# Adafruit_Wii_Nunchuck_Breakout_Adapter.net
KiCad netlist of a schematic drawn in EAGLE
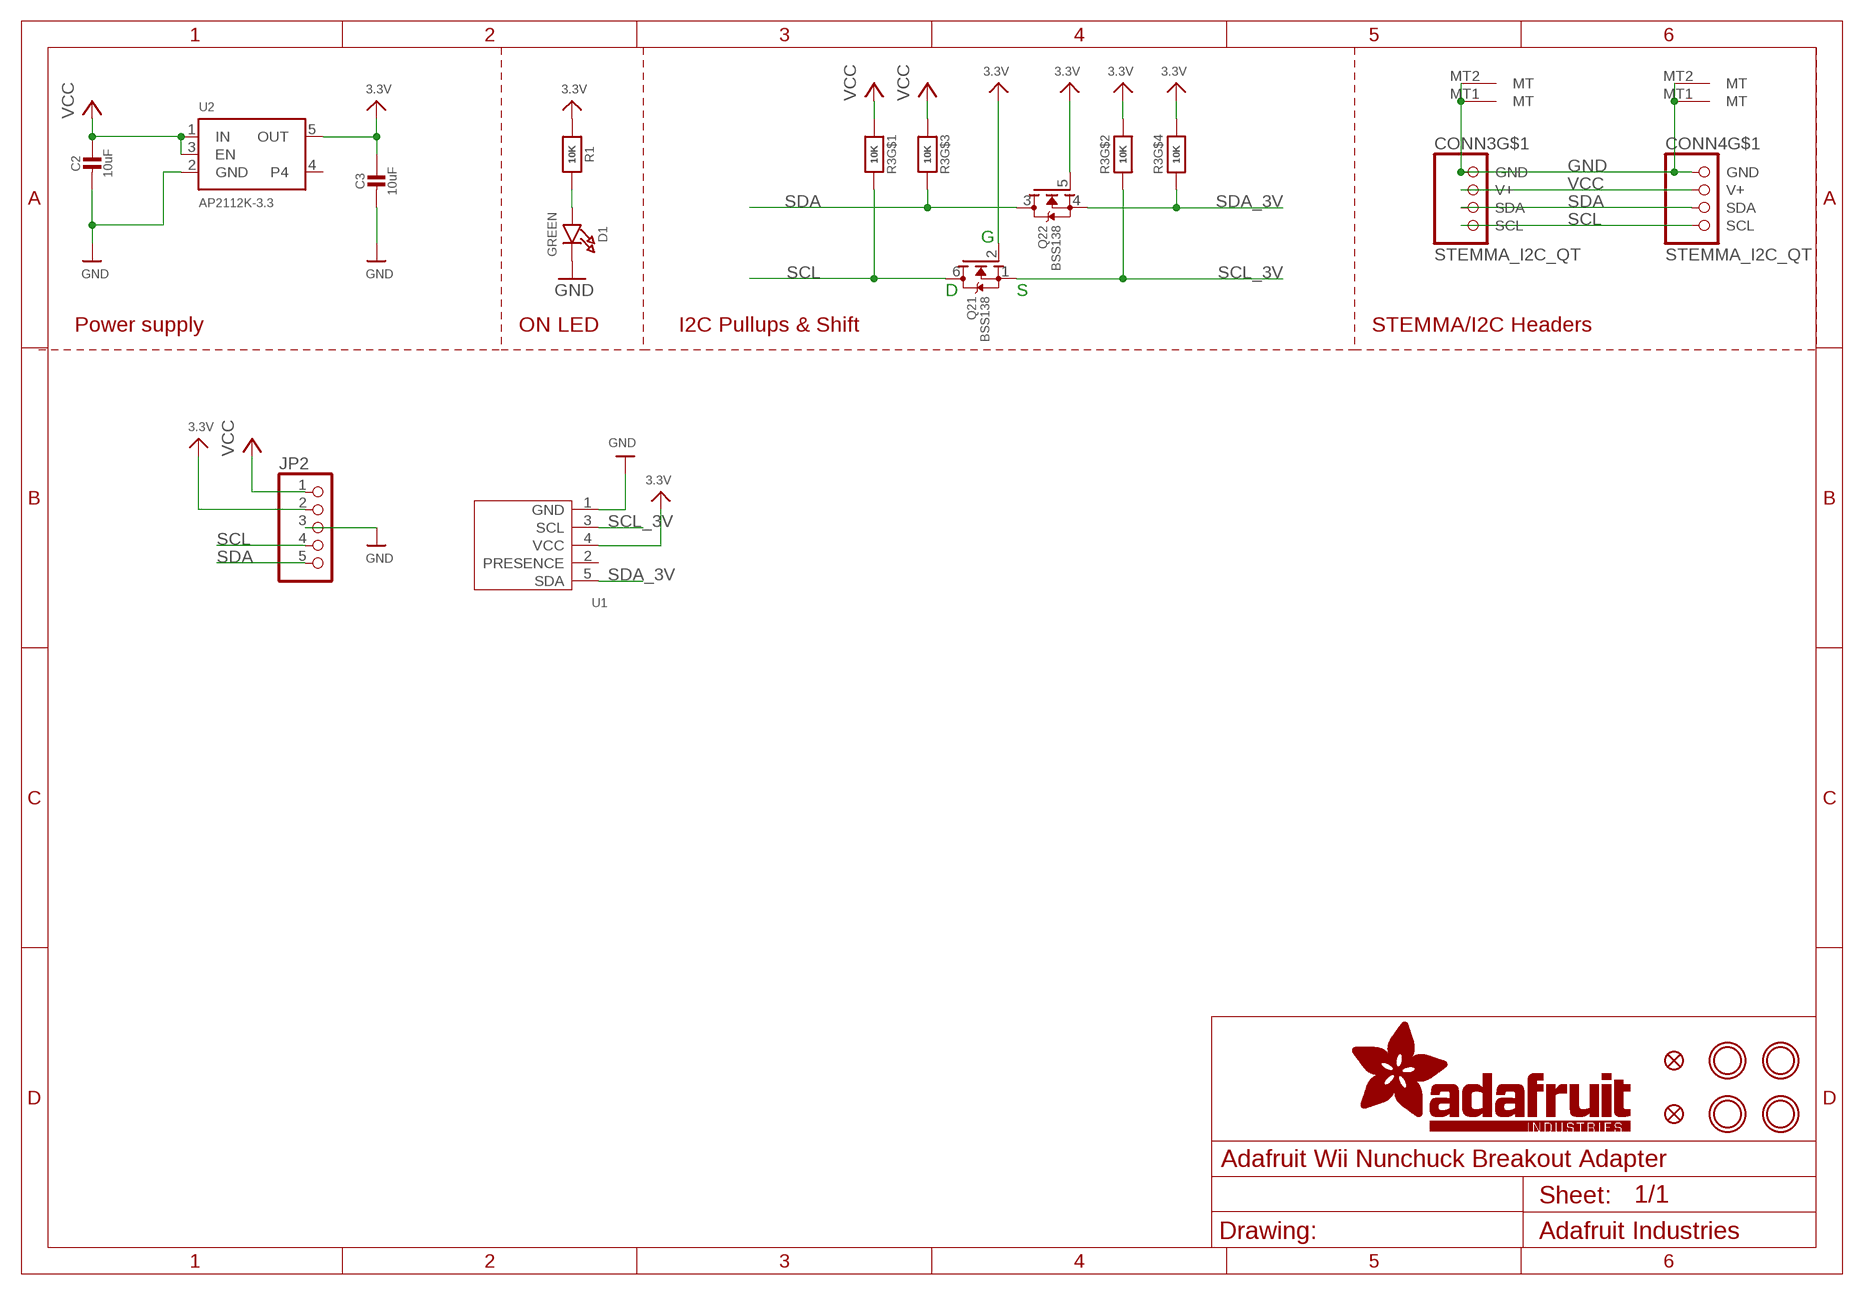
[diagram p0: schematic, sheet 1]

(export (version "E")
  (design (tool "Eeschema 10.0.6"))
  (components
    (comp (ref "C2")
      (value "10uF")
      (footprint "eagle-import:0805-NO")
      (libsource (lib "eagle-import") (part "CAP_CERAMIC0805-NOOUTLINE"))
    )
    (comp (ref "C3")
      (value "10uF")
      (footprint "eagle-import:0805-NO")
      (libsource (lib "eagle-import") (part "CAP_CERAMIC0805-NOOUTLINE"))
    )
    (comp (ref "CONN3")
      (value "STEMMA_I2C_QT")
      (footprint "eagle-import:JST_SH4")
      (libsource (lib "eagle-import") (part "STEMMA_I2C_QT"))
    )
    (comp (ref "CONN4")
      (value "STEMMA_I2C_QT")
      (footprint "eagle-import:JST_SH4")
      (libsource (lib "eagle-import") (part "STEMMA_I2C_QT"))
    )
    (comp (ref "D1")
      (value "GREEN")
      (footprint "eagle-import:CHIPLED_0603_NOOUTLINE")
      (libsource (lib "eagle-import") (part "LED0603_NOOUTLINE"))
    )
    (comp (ref "FID3")
      (value "FIDUCIAL_1MM")
      (footprint "eagle-import:FIDUCIAL_1MM")
      (libsource (lib "eagle-import") (part "FIDUCIAL_1MM"))
    )
    (comp (ref "FID4")
      (value "FIDUCIAL_1MM")
      (footprint "eagle-import:FIDUCIAL_1MM")
      (libsource (lib "eagle-import") (part "FIDUCIAL_1MM"))
    )
    (comp (ref "JP2")
      (value "HEADER-1X570MIL")
      (footprint "eagle-import:1X05_ROUND_70")
      (libsource (lib "eagle-import") (part "HEADER-1X570MIL"))
    )
    (comp (ref "Q2")
      (value "BSS138")
      (footprint "eagle-import:SOT363")
      (libsource (lib "eagle-import") (part "MOSFET-N_DUAL"))
    )
    (comp (ref "R1")
      (value "10K")
      (footprint "eagle-import:0603-NO")
      (libsource (lib "eagle-import") (part "RESISTOR_0603_NOOUT"))
    )
    (comp (ref "R3")
      (value "10K")
      (footprint "eagle-import:RESPACK_4X0603")
      (libsource (lib "eagle-import") (part "RESISTOR_4PACK"))
    )
    (comp (ref "U$1")
      (value "MOUNTINGHOLE2.5")
      (footprint "eagle-import:MOUNTINGHOLE_2.5_PLATED")
      (libsource (lib "eagle-import") (part "MOUNTINGHOLE2.5"))
    )
    (comp (ref "U$17")
      (value "MOUNTINGHOLE2.5")
      (footprint "eagle-import:MOUNTINGHOLE_2.5_PLATED")
      (libsource (lib "eagle-import") (part "MOUNTINGHOLE2.5"))
    )
    (comp (ref "U$19")
      (value "MOUNTINGHOLE2.5")
      (footprint "eagle-import:MOUNTINGHOLE_2.5_PLATED")
      (libsource (lib "eagle-import") (part "MOUNTINGHOLE2.5"))
    )
    (comp (ref "U$21")
      (value "MOUNTINGHOLE2.5")
      (footprint "eagle-import:MOUNTINGHOLE_2.5_PLATED")
      (libsource (lib "eagle-import") (part "MOUNTINGHOLE2.5"))
    )
    (comp (ref "U1")
      (value "WIICHUCK")
      (footprint "eagle-import:WIICHUCK")
      (libsource (lib "eagle-import") (part "WIICHUCK"))
    )
    (comp (ref "U2")
      (value "AP2112K-3.3")
      (footprint "eagle-import:SOT23-5")
      (libsource (lib "eagle-import") (part "VREG_SOT23-5"))
    )
  )
  (nets
    (net (code "1") (name "/SCL") (class "Default")
      (node (ref "CONN3") (pin "4") (pinfunction "SCL_4") (pintype "passive"))
      (node (ref "CONN4") (pin "4") (pinfunction "SCL_4") (pintype "passive"))
      (node (ref "JP2") (pin "4") (pinfunction "4_4") (pintype "passive"))
      (node (ref "Q2") (pin "6") (pinfunction "D_6") (pintype "bidirectional"))
      (node (ref "R3") (pin "8") (pinfunction "2_8") (pintype "passive"))
    )
    (net (code "2") (name "/SCL_3V") (class "Default")
      (node (ref "Q2") (pin "1") (pinfunction "S_1") (pintype "bidirectional"))
      (node (ref "R3") (pin "7") (pinfunction "2_7") (pintype "passive"))
      (node (ref "U1") (pin "3") (pinfunction "SCL_3") (pintype "bidirectional"))
    )
    (net (code "3") (name "/SDA") (class "Default")
      (node (ref "CONN3") (pin "3") (pinfunction "SDA_3") (pintype "passive"))
      (node (ref "CONN4") (pin "3") (pinfunction "SDA_3") (pintype "passive"))
      (node (ref "JP2") (pin "5") (pinfunction "5_5") (pintype "passive"))
      (node (ref "Q2") (pin "3") (pinfunction "D_3") (pintype "bidirectional"))
      (node (ref "R3") (pin "6") (pinfunction "2_6") (pintype "passive"))
    )
    (net (code "4") (name "/SDA_3V") (class "Default")
      (node (ref "Q2") (pin "4") (pinfunction "S_4") (pintype "bidirectional"))
      (node (ref "R3") (pin "5") (pinfunction "2_5") (pintype "passive"))
      (node (ref "U1") (pin "5") (pinfunction "SDA_5") (pintype "bidirectional"))
    )
    (net (code "5") (name "3.3V") (class "Default")
      (node (ref "C3") (pin "1") (pinfunction "1_1") (pintype "passive"))
      (node (ref "JP2") (pin "2") (pinfunction "2_2") (pintype "passive"))
      (node (ref "Q2") (pin "2") (pinfunction "G_2") (pintype "bidirectional"))
      (node (ref "Q2") (pin "5") (pinfunction "G_5") (pintype "bidirectional"))
      (node (ref "R1") (pin "1") (pinfunction "1_1") (pintype "passive"))
      (node (ref "R3") (pin "2") (pinfunction "1_2") (pintype "passive"))
      (node (ref "R3") (pin "4") (pinfunction "1_4") (pintype "passive"))
      (node (ref "U1") (pin "4") (pinfunction "VCC_4") (pintype "power_in"))
      (node (ref "U2") (pin "5") (pinfunction "OUT_5") (pintype "power_in"))
    )
    (net (code "6") (name "GND") (class "Default")
      (node (ref "C2") (pin "2") (pinfunction "2_2") (pintype "passive"))
      (node (ref "C3") (pin "2") (pinfunction "2_2") (pintype "passive"))
      (node (ref "CONN3") (pin "1") (pinfunction "GND_1") (pintype "passive"))
      (node (ref "CONN3") (pin "MT1") (pinfunction "MT_MT1") (pintype "bidirectional"))
      (node (ref "CONN3") (pin "MT2") (pinfunction "MT_MT2") (pintype "bidirectional"))
      (node (ref "CONN4") (pin "1") (pinfunction "GND_1") (pintype "passive"))
      (node (ref "CONN4") (pin "MT1") (pinfunction "MT_MT1") (pintype "bidirectional"))
      (node (ref "CONN4") (pin "MT2") (pinfunction "MT_MT2") (pintype "bidirectional"))
      (node (ref "D1") (pin "C") (pinfunction "C_C") (pintype "passive"))
      (node (ref "JP2") (pin "3") (pinfunction "3_3") (pintype "passive"))
      (node (ref "U1") (pin "1") (pinfunction "GND_1") (pintype "power_in"))
      (node (ref "U2") (pin "2") (pinfunction "GND_2") (pintype "power_in"))
    )
    (net (code "7") (name "Net-(D1-PadA)") (class "Default")
      (node (ref "D1") (pin "A") (pinfunction "A_A") (pintype "passive"))
      (node (ref "R1") (pin "2") (pinfunction "2_2") (pintype "passive"))
    )
    (net (code "8") (name "VCC") (class "Default")
      (node (ref "C2") (pin "1") (pinfunction "1_1") (pintype "passive"))
      (node (ref "CONN3") (pin "2") (pinfunction "V+_2") (pintype "passive"))
      (node (ref "CONN4") (pin "2") (pinfunction "V+_2") (pintype "passive"))
      (node (ref "JP2") (pin "1") (pinfunction "1_1") (pintype "passive"))
      (node (ref "R3") (pin "1") (pinfunction "1_1") (pintype "passive"))
      (node (ref "R3") (pin "3") (pinfunction "1_3") (pintype "passive"))
      (node (ref "U2") (pin "1") (pinfunction "IN_1") (pintype "power_in"))
      (node (ref "U2") (pin "3") (pinfunction "EN_3") (pintype "input"))
    )
    (net (code "9") (name "unconnected-(U1-PRESENCE-Pad2)") (class "Default")
      (node (ref "U1") (pin "2") (pinfunction "PRESENCE_2") (pintype "passive"))
    )
    (net (code "10") (name "unconnected-(U2-P4-Pad4)") (class "Default")
      (node (ref "U2") (pin "4") (pinfunction "P4_4") (pintype "bidirectional"))
    )
  )
)
